# ACC.net
KiCad netlist of a schematic drawn in EAGLE
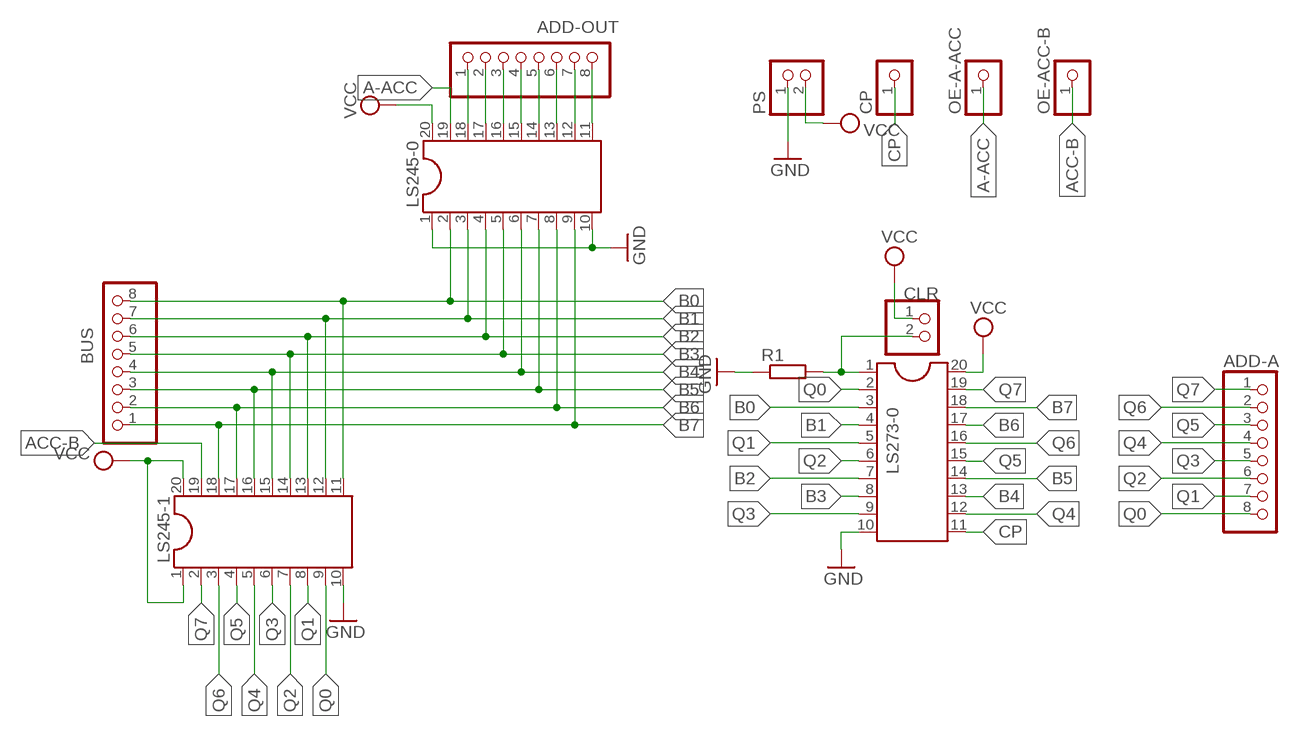
[diagram p0: schematic, sheet 1]

(export (version "E")
  (design (tool "Eeschema 10.0.6"))
  (components
    (comp (ref "ADD-A")
      (value "PINHD-1X8")
      (footprint "eagle-import:1X08")
      (libsource (lib "eagle-import") (part "PINHD-1X8"))
    )
    (comp (ref "ADD-OUT")
      (value "PINHD-1X8")
      (footprint "eagle-import:1X08")
      (libsource (lib "eagle-import") (part "PINHD-1X8"))
    )
    (comp (ref "BUS")
      (value "PINHD-1X8")
      (footprint "eagle-import:1X08")
      (libsource (lib "eagle-import") (part "PINHD-1X8"))
    )
    (comp (ref "CLR")
      (value "PINHD-1X2")
      (footprint "eagle-import:1X02")
      (libsource (lib "eagle-import") (part "PINHD-1X2"))
    )
    (comp (ref "CP")
      (value "PINHD-1X1")
      (footprint "eagle-import:1X01")
      (libsource (lib "eagle-import") (part "PINHD-1X1"))
    )
    (comp (ref "LS245-0")
      (value "DIL20S")
      (footprint "eagle-import:SOCKET-20")
      (libsource (lib "eagle-import") (part "DIL20S"))
    )
    (comp (ref "LS245-1")
      (value "DIL20S")
      (footprint "eagle-import:SOCKET-20")
      (libsource (lib "eagle-import") (part "DIL20S"))
    )
    (comp (ref "LS273-0")
      (value "DIL20S")
      (footprint "eagle-import:SOCKET-20")
      (libsource (lib "eagle-import") (part "DIL20S"))
    )
    (comp (ref "OE-A-ACC")
      (value "PINHD-1X1")
      (footprint "eagle-import:1X01")
      (libsource (lib "eagle-import") (part "PINHD-1X1"))
    )
    (comp (ref "OE-ACC-B")
      (value "PINHD-1X1")
      (footprint "eagle-import:1X01")
      (libsource (lib "eagle-import") (part "PINHD-1X1"))
    )
    (comp (ref "PS")
      (value "PINHD-1X2")
      (footprint "eagle-import:1X02")
      (libsource (lib "eagle-import") (part "PINHD-1X2"))
    )
    (comp (ref "R1")
      (value "R-EU_0204/7")
      (footprint "eagle-import:0204_7")
      (libsource (lib "eagle-import") (part "R-EU_0204/7"))
    )
  )
  (nets
    (net (code "1") (name "A-ACC") (class "Default")
      (node (ref "LS245-0") (pin "19") (pinfunction "19_19") (pintype "passive"))
      (node (ref "OE-A-ACC") (pin "1") (pinfunction "1_1") (pintype "passive"))
    )
    (net (code "2") (name "ACC-B") (class "Default")
      (node (ref "LS245-1") (pin "19") (pinfunction "19_19") (pintype "passive"))
      (node (ref "OE-ACC-B") (pin "1") (pinfunction "1_1") (pintype "passive"))
    )
    (net (code "3") (name "B0") (class "Default")
      (node (ref "BUS") (pin "8") (pinfunction "8_8") (pintype "passive"))
      (node (ref "LS245-0") (pin "2") (pinfunction "2_2") (pintype "passive"))
      (node (ref "LS245-1") (pin "11") (pinfunction "11_11") (pintype "passive"))
      (node (ref "LS273-0") (pin "3") (pinfunction "3_3") (pintype "passive"))
    )
    (net (code "4") (name "B1") (class "Default")
      (node (ref "BUS") (pin "7") (pinfunction "7_7") (pintype "passive"))
      (node (ref "LS245-0") (pin "3") (pinfunction "3_3") (pintype "passive"))
      (node (ref "LS245-1") (pin "12") (pinfunction "12_12") (pintype "passive"))
      (node (ref "LS273-0") (pin "4") (pinfunction "4_4") (pintype "passive"))
    )
    (net (code "5") (name "B2") (class "Default")
      (node (ref "BUS") (pin "6") (pinfunction "6_6") (pintype "passive"))
      (node (ref "LS245-0") (pin "4") (pinfunction "4_4") (pintype "passive"))
      (node (ref "LS245-1") (pin "13") (pinfunction "13_13") (pintype "passive"))
      (node (ref "LS273-0") (pin "7") (pinfunction "7_7") (pintype "passive"))
    )
    (net (code "6") (name "B3") (class "Default")
      (node (ref "BUS") (pin "5") (pinfunction "5_5") (pintype "passive"))
      (node (ref "LS245-0") (pin "5") (pinfunction "5_5") (pintype "passive"))
      (node (ref "LS245-1") (pin "14") (pinfunction "14_14") (pintype "passive"))
      (node (ref "LS273-0") (pin "8") (pinfunction "8_8") (pintype "passive"))
    )
    (net (code "7") (name "B4") (class "Default")
      (node (ref "BUS") (pin "4") (pinfunction "4_4") (pintype "passive"))
      (node (ref "LS245-0") (pin "6") (pinfunction "6_6") (pintype "passive"))
      (node (ref "LS245-1") (pin "15") (pinfunction "15_15") (pintype "passive"))
      (node (ref "LS273-0") (pin "13") (pinfunction "13_13") (pintype "passive"))
    )
    (net (code "8") (name "B5") (class "Default")
      (node (ref "BUS") (pin "3") (pinfunction "3_3") (pintype "passive"))
      (node (ref "LS245-0") (pin "7") (pinfunction "7_7") (pintype "passive"))
      (node (ref "LS245-1") (pin "16") (pinfunction "16_16") (pintype "passive"))
      (node (ref "LS273-0") (pin "14") (pinfunction "14_14") (pintype "passive"))
    )
    (net (code "9") (name "B6") (class "Default")
      (node (ref "BUS") (pin "2") (pinfunction "2_2") (pintype "passive"))
      (node (ref "LS245-0") (pin "8") (pinfunction "8_8") (pintype "passive"))
      (node (ref "LS245-1") (pin "17") (pinfunction "17_17") (pintype "passive"))
      (node (ref "LS273-0") (pin "17") (pinfunction "17_17") (pintype "passive"))
    )
    (net (code "10") (name "B7") (class "Default")
      (node (ref "BUS") (pin "1") (pinfunction "1_1") (pintype "passive"))
      (node (ref "LS245-0") (pin "9") (pinfunction "9_9") (pintype "passive"))
      (node (ref "LS245-1") (pin "18") (pinfunction "18_18") (pintype "passive"))
      (node (ref "LS273-0") (pin "18") (pinfunction "18_18") (pintype "passive"))
    )
    (net (code "11") (name "CP") (class "Default")
      (node (ref "CP") (pin "1") (pinfunction "1_1") (pintype "passive"))
      (node (ref "LS273-0") (pin "11") (pinfunction "11_11") (pintype "passive"))
    )
    (net (code "12") (name "GND") (class "Default")
      (node (ref "LS245-0") (pin "1") (pinfunction "1_1") (pintype "passive"))
      (node (ref "LS245-0") (pin "10") (pinfunction "10_10") (pintype "passive"))
      (node (ref "LS245-1") (pin "10") (pinfunction "10_10") (pintype "passive"))
      (node (ref "LS273-0") (pin "10") (pinfunction "10_10") (pintype "passive"))
      (node (ref "PS") (pin "1") (pinfunction "1_1") (pintype "passive"))
      (node (ref "R1") (pin "1") (pinfunction "1_1") (pintype "passive"))
    )
    (net (code "13") (name "Net-(ADD-OUT-Pad1)") (class "Default")
      (node (ref "ADD-OUT") (pin "1") (pinfunction "1_1") (pintype "passive"))
      (node (ref "LS245-0") (pin "18") (pinfunction "18_18") (pintype "passive"))
    )
    (net (code "14") (name "Net-(ADD-OUT-Pad2)") (class "Default")
      (node (ref "ADD-OUT") (pin "2") (pinfunction "2_2") (pintype "passive"))
      (node (ref "LS245-0") (pin "17") (pinfunction "17_17") (pintype "passive"))
    )
    (net (code "15") (name "Net-(ADD-OUT-Pad3)") (class "Default")
      (node (ref "ADD-OUT") (pin "3") (pinfunction "3_3") (pintype "passive"))
      (node (ref "LS245-0") (pin "16") (pinfunction "16_16") (pintype "passive"))
    )
    (net (code "16") (name "Net-(ADD-OUT-Pad4)") (class "Default")
      (node (ref "ADD-OUT") (pin "4") (pinfunction "4_4") (pintype "passive"))
      (node (ref "LS245-0") (pin "15") (pinfunction "15_15") (pintype "passive"))
    )
    (net (code "17") (name "Net-(ADD-OUT-Pad5)") (class "Default")
      (node (ref "ADD-OUT") (pin "5") (pinfunction "5_5") (pintype "passive"))
      (node (ref "LS245-0") (pin "14") (pinfunction "14_14") (pintype "passive"))
    )
    (net (code "18") (name "Net-(ADD-OUT-Pad6)") (class "Default")
      (node (ref "ADD-OUT") (pin "6") (pinfunction "6_6") (pintype "passive"))
      (node (ref "LS245-0") (pin "13") (pinfunction "13_13") (pintype "passive"))
    )
    (net (code "19") (name "Net-(ADD-OUT-Pad7)") (class "Default")
      (node (ref "ADD-OUT") (pin "7") (pinfunction "7_7") (pintype "passive"))
      (node (ref "LS245-0") (pin "12") (pinfunction "12_12") (pintype "passive"))
    )
    (net (code "20") (name "Net-(ADD-OUT-Pad8)") (class "Default")
      (node (ref "ADD-OUT") (pin "8") (pinfunction "8_8") (pintype "passive"))
      (node (ref "LS245-0") (pin "11") (pinfunction "11_11") (pintype "passive"))
    )
    (net (code "21") (name "Net-(CLR-Pad2)") (class "Default")
      (node (ref "CLR") (pin "2") (pinfunction "2_2") (pintype "passive"))
      (node (ref "LS273-0") (pin "1") (pinfunction "1_1") (pintype "passive"))
      (node (ref "R1") (pin "2") (pinfunction "2_2") (pintype "passive"))
    )
    (net (code "22") (name "Q0") (class "Default")
      (node (ref "ADD-A") (pin "8") (pinfunction "8_8") (pintype "passive"))
      (node (ref "LS245-1") (pin "9") (pinfunction "9_9") (pintype "passive"))
      (node (ref "LS273-0") (pin "2") (pinfunction "2_2") (pintype "passive"))
    )
    (net (code "23") (name "Q1") (class "Default")
      (node (ref "ADD-A") (pin "7") (pinfunction "7_7") (pintype "passive"))
      (node (ref "LS245-1") (pin "8") (pinfunction "8_8") (pintype "passive"))
      (node (ref "LS273-0") (pin "5") (pinfunction "5_5") (pintype "passive"))
    )
    (net (code "24") (name "Q2") (class "Default")
      (node (ref "ADD-A") (pin "6") (pinfunction "6_6") (pintype "passive"))
      (node (ref "LS245-1") (pin "7") (pinfunction "7_7") (pintype "passive"))
      (node (ref "LS273-0") (pin "6") (pinfunction "6_6") (pintype "passive"))
    )
    (net (code "25") (name "Q3") (class "Default")
      (node (ref "ADD-A") (pin "5") (pinfunction "5_5") (pintype "passive"))
      (node (ref "LS245-1") (pin "6") (pinfunction "6_6") (pintype "passive"))
      (node (ref "LS273-0") (pin "9") (pinfunction "9_9") (pintype "passive"))
    )
    (net (code "26") (name "Q4") (class "Default")
      (node (ref "ADD-A") (pin "4") (pinfunction "4_4") (pintype "passive"))
      (node (ref "LS245-1") (pin "5") (pinfunction "5_5") (pintype "passive"))
      (node (ref "LS273-0") (pin "12") (pinfunction "12_12") (pintype "passive"))
    )
    (net (code "27") (name "Q5") (class "Default")
      (node (ref "ADD-A") (pin "3") (pinfunction "3_3") (pintype "passive"))
      (node (ref "LS245-1") (pin "4") (pinfunction "4_4") (pintype "passive"))
      (node (ref "LS273-0") (pin "15") (pinfunction "15_15") (pintype "passive"))
    )
    (net (code "28") (name "Q6") (class "Default")
      (node (ref "ADD-A") (pin "2") (pinfunction "2_2") (pintype "passive"))
      (node (ref "LS245-1") (pin "3") (pinfunction "3_3") (pintype "passive"))
      (node (ref "LS273-0") (pin "16") (pinfunction "16_16") (pintype "passive"))
    )
    (net (code "29") (name "Q7") (class "Default")
      (node (ref "ADD-A") (pin "1") (pinfunction "1_1") (pintype "passive"))
      (node (ref "LS245-1") (pin "2") (pinfunction "2_2") (pintype "passive"))
      (node (ref "LS273-0") (pin "19") (pinfunction "19_19") (pintype "passive"))
    )
    (net (code "30") (name "VCC") (class "Default")
      (node (ref "CLR") (pin "1") (pinfunction "1_1") (pintype "passive"))
      (node (ref "LS245-0") (pin "20") (pinfunction "20_20") (pintype "passive"))
      (node (ref "LS245-1") (pin "1") (pinfunction "1_1") (pintype "passive"))
      (node (ref "LS245-1") (pin "20") (pinfunction "20_20") (pintype "passive"))
      (node (ref "LS273-0") (pin "20") (pinfunction "20_20") (pintype "passive"))
      (node (ref "PS") (pin "2") (pinfunction "2_2") (pintype "passive"))
    )
  )
)
